# EEPROM.net
KiCad netlist of a schematic drawn in Altium Designer
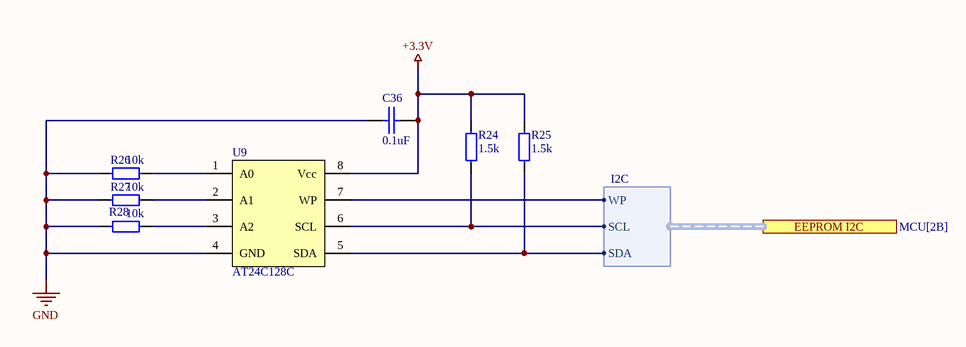
[diagram p0: EEPROM.SchDoc]

(export (version "E")
  (design (tool "Eeschema 10.0.6"))
  (components
    (comp (ref "C36")
      (value "0.1uF")
      (footprint "0805 Capicator")
      (description "0.1uF X7R 25V 10% 0805")
      (fields
        (field (name "MANUFACTURER") "Murata Manufacturing")
        (field (name "PART NUMBER") "GRM21BR71E104KA01L")
      )
      (libsource (lib "BRT_Components") (part "Cap 0.1uF (0805)"))
    )
    (comp (ref "R24")
      (value "1.5k")
      (footprint "0805 Resistor")
      (description "0.125W 0805 1.5k, 1%")
      (fields (field (name "PART NUMBER") "RC0805FR-071K5L") (field (name "MANUFACTURER") "Taiwan"))
      (libsource (lib "BRT_Components") (part "Res 1.5k (0805)"))
    )
    (comp (ref "R25")
      (value "1.5k")
      (footprint "0805 Resistor")
      (description "0.125W 0805 1.5k, 1%")
      (fields (field (name "PART NUMBER") "RC0805FR-071K5L") (field (name "MANUFACTURER") "Taiwan"))
      (libsource (lib "BRT_Components") (part "Res 1.5k (0805)"))
    )
    (comp (ref "R26")
      (value "10k")
      (footprint "0805 Resistor")
      (description "0.125W 0805 10k, 1%")
      (fields (field (name "PART NUMBER") "RC0805FR-0710KL") (field (name "MANUFACTURER") "Taiwan"))
      (libsource (lib "BRT_Components") (part "Res 10k (0805)"))
    )
    (comp (ref "R27")
      (value "10k")
      (footprint "0805 Resistor")
      (description "0.125W 0805 10k, 1%")
      (fields (field (name "PART NUMBER") "RC0805FR-0710KL") (field (name "MANUFACTURER") "Taiwan"))
      (libsource (lib "BRT_Components") (part "Res 10k (0805)"))
    )
    (comp (ref "R28")
      (value "10k")
      (footprint "0805 Resistor")
      (description "0.125W 0805 10k, 1%")
      (fields (field (name "PART NUMBER") "RC0805FR-0710KL") (field (name "MANUFACTURER") "Taiwan"))
      (libsource (lib "BRT_Components") (part "Res 10k (0805)"))
    )
    (comp (ref "U9")
      (value "AT24C128C")
      (footprint "SOIC-8")
      (description "I2C-Compatible (2-Wire) Serial EEPROM 128-Kbit")
      (libsource (lib "Altium_Library") (part "EEPROM AT24C128C"))
    )
  )
  (nets
    (net (code "2") (name "+3.3V") (class "Default")
      (node (ref "C36") (pin "1") (pinfunction "1_1") (pintype "passive"))
      (node (ref "R24") (pin "2") (pinfunction "2_2") (pintype "passive"))
      (node (ref "R25") (pin "2") (pinfunction "2_2") (pintype "passive"))
      (node (ref "U9") (pin "8") (pinfunction "Vcc_8") (pintype "passive"))
    )
    (net (code "3") (name "/SCL") (class "Default")
      (node (ref "R24") (pin "1") (pinfunction "1_1") (pintype "passive"))
      (node (ref "U9") (pin "6") (pinfunction "SCL_6") (pintype "passive"))
    )
    (net (code "4") (name "/SDA") (class "Default")
      (node (ref "R25") (pin "1") (pinfunction "1_1") (pintype "passive"))
      (node (ref "U9") (pin "5") (pinfunction "SDA_5") (pintype "passive"))
    )
    (net (code "5") (name "/WP") (class "Default")
      (node (ref "U9") (pin "7") (pinfunction "WP_7") (pintype "passive"))
    )
    (net (code "7") (name "GND") (class "Default")
      (node (ref "C36") (pin "2") (pinfunction "2_2") (pintype "passive"))
      (node (ref "R26") (pin "1") (pinfunction "1_1") (pintype "passive"))
      (node (ref "R27") (pin "1") (pinfunction "1_1") (pintype "passive"))
      (node (ref "R28") (pin "1") (pinfunction "1_1") (pintype "passive"))
      (node (ref "U9") (pin "4") (pinfunction "GND_4") (pintype "passive"))
    )
    (net (code "8") (name "Net-(U9-A0)") (class "Default")
      (node (ref "R26") (pin "2") (pinfunction "2_2") (pintype "passive"))
      (node (ref "U9") (pin "1") (pinfunction "A0_1") (pintype "passive"))
    )
    (net (code "9") (name "Net-(U9-A1)") (class "Default")
      (node (ref "R27") (pin "2") (pinfunction "2_2") (pintype "passive"))
      (node (ref "U9") (pin "2") (pinfunction "A1_2") (pintype "passive"))
    )
    (net (code "10") (name "Net-(U9-A2)") (class "Default")
      (node (ref "R28") (pin "2") (pinfunction "2_2") (pintype "passive"))
      (node (ref "U9") (pin "3") (pinfunction "A2_3") (pintype "passive"))
    )
  )
)
